# OSD.net
KiCad netlist of a schematic drawn in Altium Designer
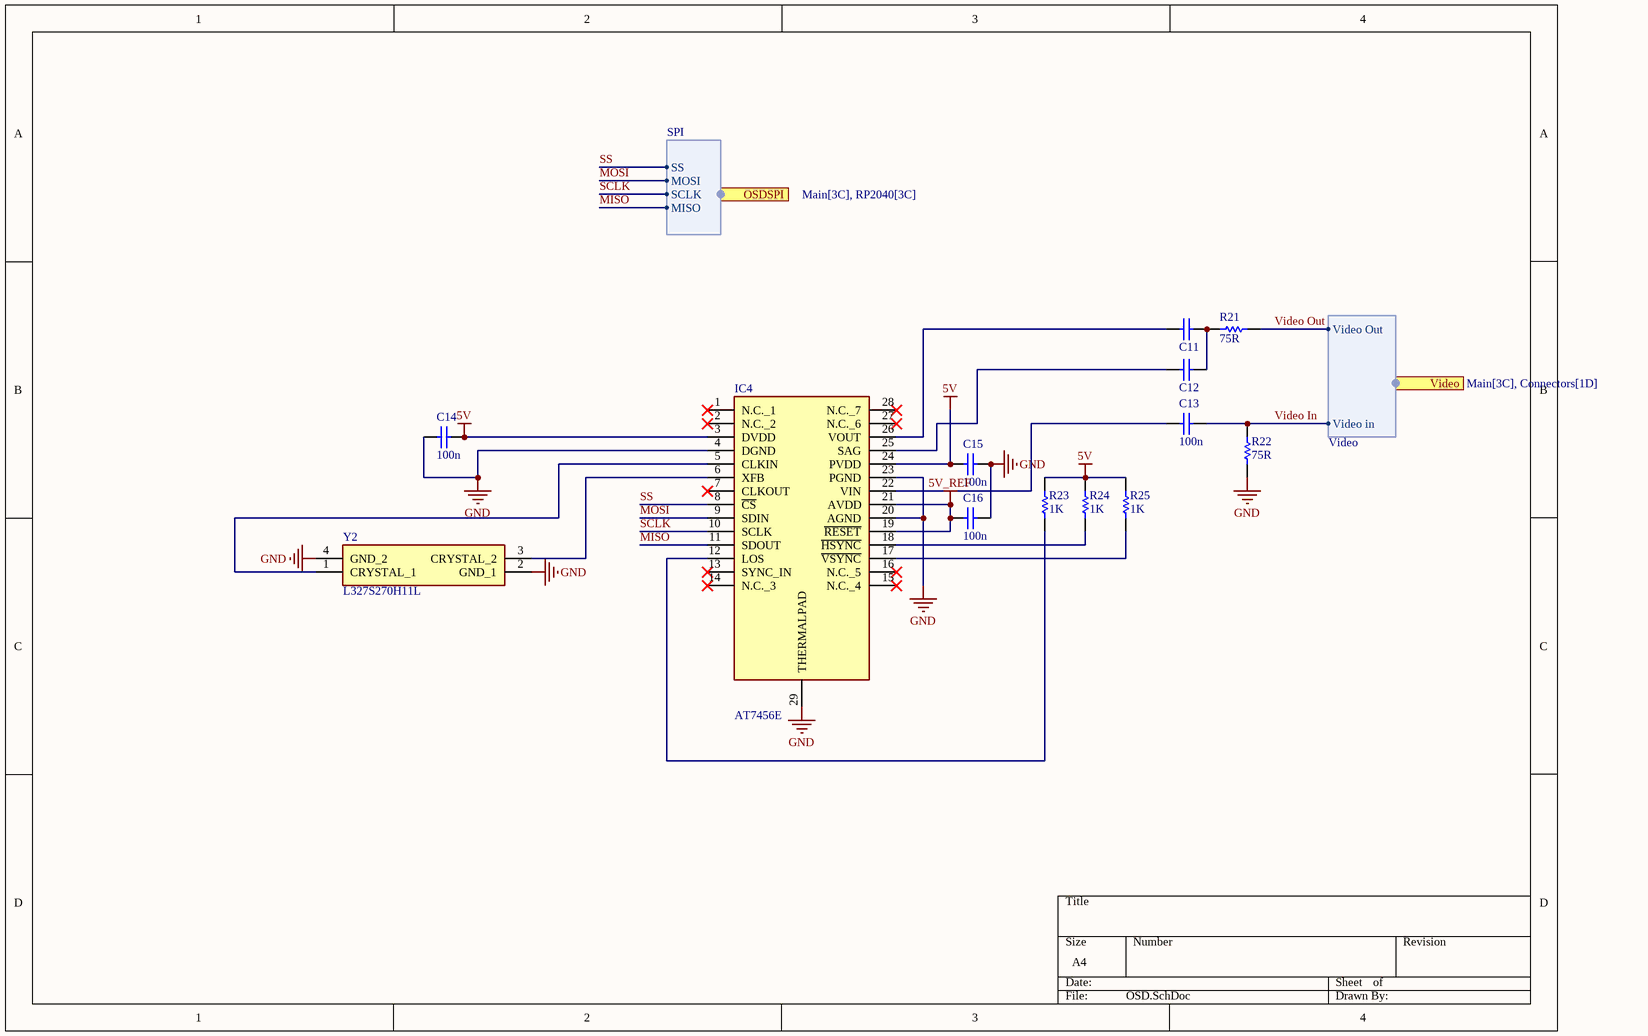
[diagram p0: OSD.SchDoc]

(export (version "E")
  (design (tool "Eeschema 10.0.6"))
  (components
    (comp (ref "C11")
      (value "10µF")
      (footprint "WCAP-CSGP_0603_L1.6W0.8H0.8_Reflow")
      (description "WCAP-CSGP Multilayer Ceramic Chip Capacitor, General Purpose, size 0603, X5R, 10µF, 25VDC")
      (fields
        (field (name "MANUFACTURER PART NUMBER") "885012106031")
        (field (name "MANUFACTURER") "Wurth Elektronik")
      )
      (libsource (lib "Altium_WCAP-CSGP (rev22e)") (part "885012106031"))
    )
    (comp (ref "C12")
      (value "10µF")
      (footprint "WCAP-CSGP_0603_L1.6W0.8H0.8_Reflow")
      (description "WCAP-CSGP Multilayer Ceramic Chip Capacitor, General Purpose, size 0603, X5R, 10µF, 25VDC")
      (fields
        (field (name "MANUFACTURER PART NUMBER") "885012106031")
        (field (name "MANUFACTURER") "Wurth Elektronik")
      )
      (libsource (lib "Altium_WCAP-CSGP (rev22e)") (part "885012106031"))
    )
    (comp (ref "C13")
      (value "100n")
      (footprint "CAPC0603(1608)55_N")
      (description "Keramikvielschichtkondensator, SMD, Baureihe MC, ± 20%")
      (fields (field (name "MANUFACTURER") "Multicomp"))
      (libsource (lib "Standardbauteile") (part "Cap 100n"))
    )
    (comp (ref "C14")
      (value "100n")
      (footprint "CAPC0603(1608)55_N")
      (description "Keramikvielschichtkondensator, SMD, Baureihe MC, ± 20%")
      (fields (field (name "MANUFACTURER") "Multicomp"))
      (libsource (lib "Standardbauteile") (part "Cap 100n"))
    )
    (comp (ref "C15")
      (value "100n")
      (footprint "CAPC0603(1608)55_N")
      (description "Keramikvielschichtkondensator, SMD, Baureihe MC, ± 20%")
      (fields (field (name "MANUFACTURER") "Multicomp"))
      (libsource (lib "Standardbauteile") (part "Cap 100n"))
    )
    (comp (ref "C16")
      (value "100n")
      (footprint "CAPC0603(1608)55_N")
      (description "Keramikvielschichtkondensator, SMD, Baureihe MC, ± 20%")
      (fields (field (name "MANUFACTURER") "Multicomp"))
      (libsource (lib "Standardbauteile") (part "Cap 100n"))
    )
    (comp (ref "IC4")
      (value "AT7456E")
      (footprint "Custom Components:SOP65P640X120-29N")
      (description "Integrated Circuit")
      (libsource (lib "*") (part "AT7456E"))
    )
    (comp (ref "R21")
      (value "75R")
      (footprint "RESC0603(1608)_N")
      (description "Chipwiderstand, SMD, Baureihe MC, 1%")
      (fields (field (name "MANUFACTURER") "Multicomp"))
      (libsource (lib "Standardbauteile") (part "Res 750R"))
    )
    (comp (ref "R22")
      (value "75R")
      (footprint "RESC0603(1608)_N")
      (description "Chipwiderstand, SMD, Baureihe MC, 1%")
      (fields (field (name "MANUFACTURER") "Multicomp"))
      (libsource (lib "Standardbauteile") (part "Res 750R"))
    )
    (comp (ref "R23")
      (value "1K")
      (footprint "RESC0603(1608)_N")
      (description "Chipwiderstand, SMD, Baureihe MC, 1%")
      (fields (field (name "MANUFACTURER") "Multicomp"))
      (libsource (lib "Standardbauteile") (part "Res 1K"))
    )
    (comp (ref "R24")
      (value "1K")
      (footprint "RESC0603(1608)_N")
      (description "Chipwiderstand, SMD, Baureihe MC, 1%")
      (fields (field (name "MANUFACTURER") "Multicomp"))
      (libsource (lib "Standardbauteile") (part "Res 1K"))
    )
    (comp (ref "R25")
      (value "1K")
      (footprint "RESC0603(1608)_N")
      (description "Chipwiderstand, SMD, Baureihe MC, 1%")
      (fields (field (name "MANUFACTURER") "Multicomp"))
      (libsource (lib "Standardbauteile") (part "Res 1K"))
    )
    (comp (ref "Y2")
      (value "L327S270H11L")
      (footprint "Custom Components:SMD3225_4P12288MHZ12PF10PPM4085")
      (description "Crystal or Oscillator")
      (fields (field (name "MANUFACTURER_PART_NUMBER") "SMD-3225_4P 12.288MHZ 12PF 10PPM -40~+85℃"))
      (libsource (lib "*") (part "SMD-3225_4P_12.288MHZ_12PF_10PPM_-40~+85"))
    )
  )
  (nets
    (net (code "3") (name "/MISO") (class "Default")
      (node (ref "IC4") (pin "11") (pinfunction "SDOUT_11") (pintype "passive"))
    )
    (net (code "4") (name "/MOSI") (class "Default")
      (node (ref "IC4") (pin "9") (pinfunction "SDIN_9") (pintype "passive"))
    )
    (net (code "5") (name "/SCLK") (class "Default")
      (node (ref "IC4") (pin "10") (pinfunction "SCLK_10") (pintype "passive"))
    )
    (net (code "6") (name "/SS") (class "Default")
      (node (ref "IC4") (pin "8") (pinfunction "~{CS}_8") (pintype "passive"))
    )
    (net (code "7") (name "/Video In") (class "Default")
      (node (ref "C13") (pin "2") (pinfunction "2_2") (pintype "passive"))
      (node (ref "R22") (pin "2") (pinfunction "2_2") (pintype "passive"))
    )
    (net (code "8") (name "/Video Out") (class "Default")
      (node (ref "R21") (pin "1") (pinfunction "1_1") (pintype "passive"))
    )
    (net (code "11") (name "5V") (class "Default")
      (node (ref "C14") (pin "2") (pinfunction "2_2") (pintype "passive"))
      (node (ref "C15") (pin "1") (pinfunction "1_1") (pintype "passive"))
      (node (ref "IC4") (pin "24") (pinfunction "PVDD_24") (pintype "passive"))
      (node (ref "IC4") (pin "3") (pinfunction "DVDD_3") (pintype "passive"))
      (node (ref "R23") (pin "2") (pinfunction "2_2") (pintype "passive"))
      (node (ref "R24") (pin "2") (pinfunction "2_2") (pintype "passive"))
      (node (ref "R25") (pin "2") (pinfunction "2_2") (pintype "passive"))
    )
    (net (code "12") (name "5V_REF") (class "Default")
      (node (ref "C16") (pin "1") (pinfunction "1_1") (pintype "passive"))
      (node (ref "IC4") (pin "19") (pinfunction "~{RESET}_19") (pintype "passive"))
      (node (ref "IC4") (pin "21") (pinfunction "AVDD_21") (pintype "passive"))
    )
    (net (code "13") (name "GND") (class "Default")
      (node (ref "C14") (pin "1") (pinfunction "1_1") (pintype "passive"))
      (node (ref "C15") (pin "2") (pinfunction "2_2") (pintype "passive"))
      (node (ref "C16") (pin "2") (pinfunction "2_2") (pintype "passive"))
      (node (ref "IC4") (pin "20") (pinfunction "AGND_20") (pintype "passive"))
      (node (ref "IC4") (pin "23") (pinfunction "PGND_23") (pintype "passive"))
      (node (ref "IC4") (pin "29") (pinfunction "THERMALPAD_29") (pintype "passive"))
      (node (ref "IC4") (pin "4") (pinfunction "DGND_4") (pintype "passive"))
      (node (ref "R22") (pin "1") (pinfunction "1_1") (pintype "passive"))
      (node (ref "Y2") (pin "2") (pinfunction "GND_1_2") (pintype "passive"))
      (node (ref "Y2") (pin "4") (pinfunction "GND_2_4") (pintype "passive"))
    )
    (net (code "14") (name "Net-(C11-Pad2)") (class "Default")
      (node (ref "C11") (pin "2") (pinfunction "2_2") (pintype "passive"))
      (node (ref "C12") (pin "2") (pinfunction "2_2") (pintype "passive"))
      (node (ref "R21") (pin "2") (pinfunction "2_2") (pintype "passive"))
    )
    (net (code "15") (name "Net-(IC4-CLKIN)") (class "Default")
      (node (ref "IC4") (pin "5") (pinfunction "CLKIN_5") (pintype "passive"))
      (node (ref "Y2") (pin "1") (pinfunction "CRYSTAL_1_1") (pintype "passive"))
    )
    (net (code "16") (name "Net-(IC4-LOS)") (class "Default")
      (node (ref "IC4") (pin "12") (pinfunction "LOS_12") (pintype "passive"))
      (node (ref "R23") (pin "1") (pinfunction "1_1") (pintype "passive"))
    )
    (net (code "17") (name "Net-(IC4-SAG)") (class "Default")
      (node (ref "C12") (pin "1") (pinfunction "1_1") (pintype "passive"))
      (node (ref "IC4") (pin "25") (pinfunction "SAG_25") (pintype "passive"))
    )
    (net (code "18") (name "Net-(IC4-VIN)") (class "Default")
      (node (ref "C13") (pin "1") (pinfunction "1_1") (pintype "passive"))
      (node (ref "IC4") (pin "22") (pinfunction "VIN_22") (pintype "passive"))
    )
    (net (code "19") (name "Net-(IC4-VOUT)") (class "Default")
      (node (ref "C11") (pin "1") (pinfunction "1_1") (pintype "passive"))
      (node (ref "IC4") (pin "26") (pinfunction "VOUT_26") (pintype "passive"))
    )
    (net (code "20") (name "Net-(IC4-XFB)") (class "Default")
      (node (ref "IC4") (pin "6") (pinfunction "XFB_6") (pintype "passive"))
      (node (ref "Y2") (pin "3") (pinfunction "CRYSTAL_2_3") (pintype "passive"))
    )
    (net (code "21") (name "Net-(IC4-~{HSYNC})") (class "Default")
      (node (ref "IC4") (pin "18") (pinfunction "~{HSYNC}_18") (pintype "passive"))
      (node (ref "R24") (pin "1") (pinfunction "1_1") (pintype "passive"))
    )
    (net (code "22") (name "Net-(IC4-~{VSYNC})") (class "Default")
      (node (ref "IC4") (pin "17") (pinfunction "~{VSYNC}_17") (pintype "passive"))
      (node (ref "R25") (pin "1") (pinfunction "1_1") (pintype "passive"))
    )
    (net (code "23") (name "unconnected-(IC4-CLKOUT-Pad7)") (class "Default")
      (node (ref "IC4") (pin "7") (pinfunction "CLKOUT_7") (pintype "passive+no_connect"))
    )
    (net (code "24") (name "unconnected-(IC4-N.C._1-Pad1)") (class "Default")
      (node (ref "IC4") (pin "1") (pinfunction "N.C._1_1") (pintype "passive+no_connect"))
    )
    (net (code "25") (name "unconnected-(IC4-N.C._2-Pad2)") (class "Default")
      (node (ref "IC4") (pin "2") (pinfunction "N.C._2_2") (pintype "passive+no_connect"))
    )
    (net (code "26") (name "unconnected-(IC4-N.C._3-Pad14)") (class "Default")
      (node (ref "IC4") (pin "14") (pinfunction "N.C._3_14") (pintype "passive+no_connect"))
    )
    (net (code "27") (name "unconnected-(IC4-N.C._4-Pad15)") (class "Default")
      (node (ref "IC4") (pin "15") (pinfunction "N.C._4_15") (pintype "passive+no_connect"))
    )
    (net (code "28") (name "unconnected-(IC4-N.C._5-Pad16)") (class "Default")
      (node (ref "IC4") (pin "16") (pinfunction "N.C._5_16") (pintype "passive+no_connect"))
    )
    (net (code "29") (name "unconnected-(IC4-N.C._6-Pad27)") (class "Default")
      (node (ref "IC4") (pin "27") (pinfunction "N.C._6_27") (pintype "passive+no_connect"))
    )
    (net (code "30") (name "unconnected-(IC4-N.C._7-Pad28)") (class "Default")
      (node (ref "IC4") (pin "28") (pinfunction "N.C._7_28") (pintype "passive+no_connect"))
    )
    (net (code "31") (name "unconnected-(IC4-SYNC_IN-Pad13)") (class "Default")
      (node (ref "IC4") (pin "13") (pinfunction "SYNC_IN_13") (pintype "passive+no_connect"))
    )
  )
)
